# BLUENRG-345_REV1_Sheet1.net
KiCad netlist of a schematic drawn in Altium Designer
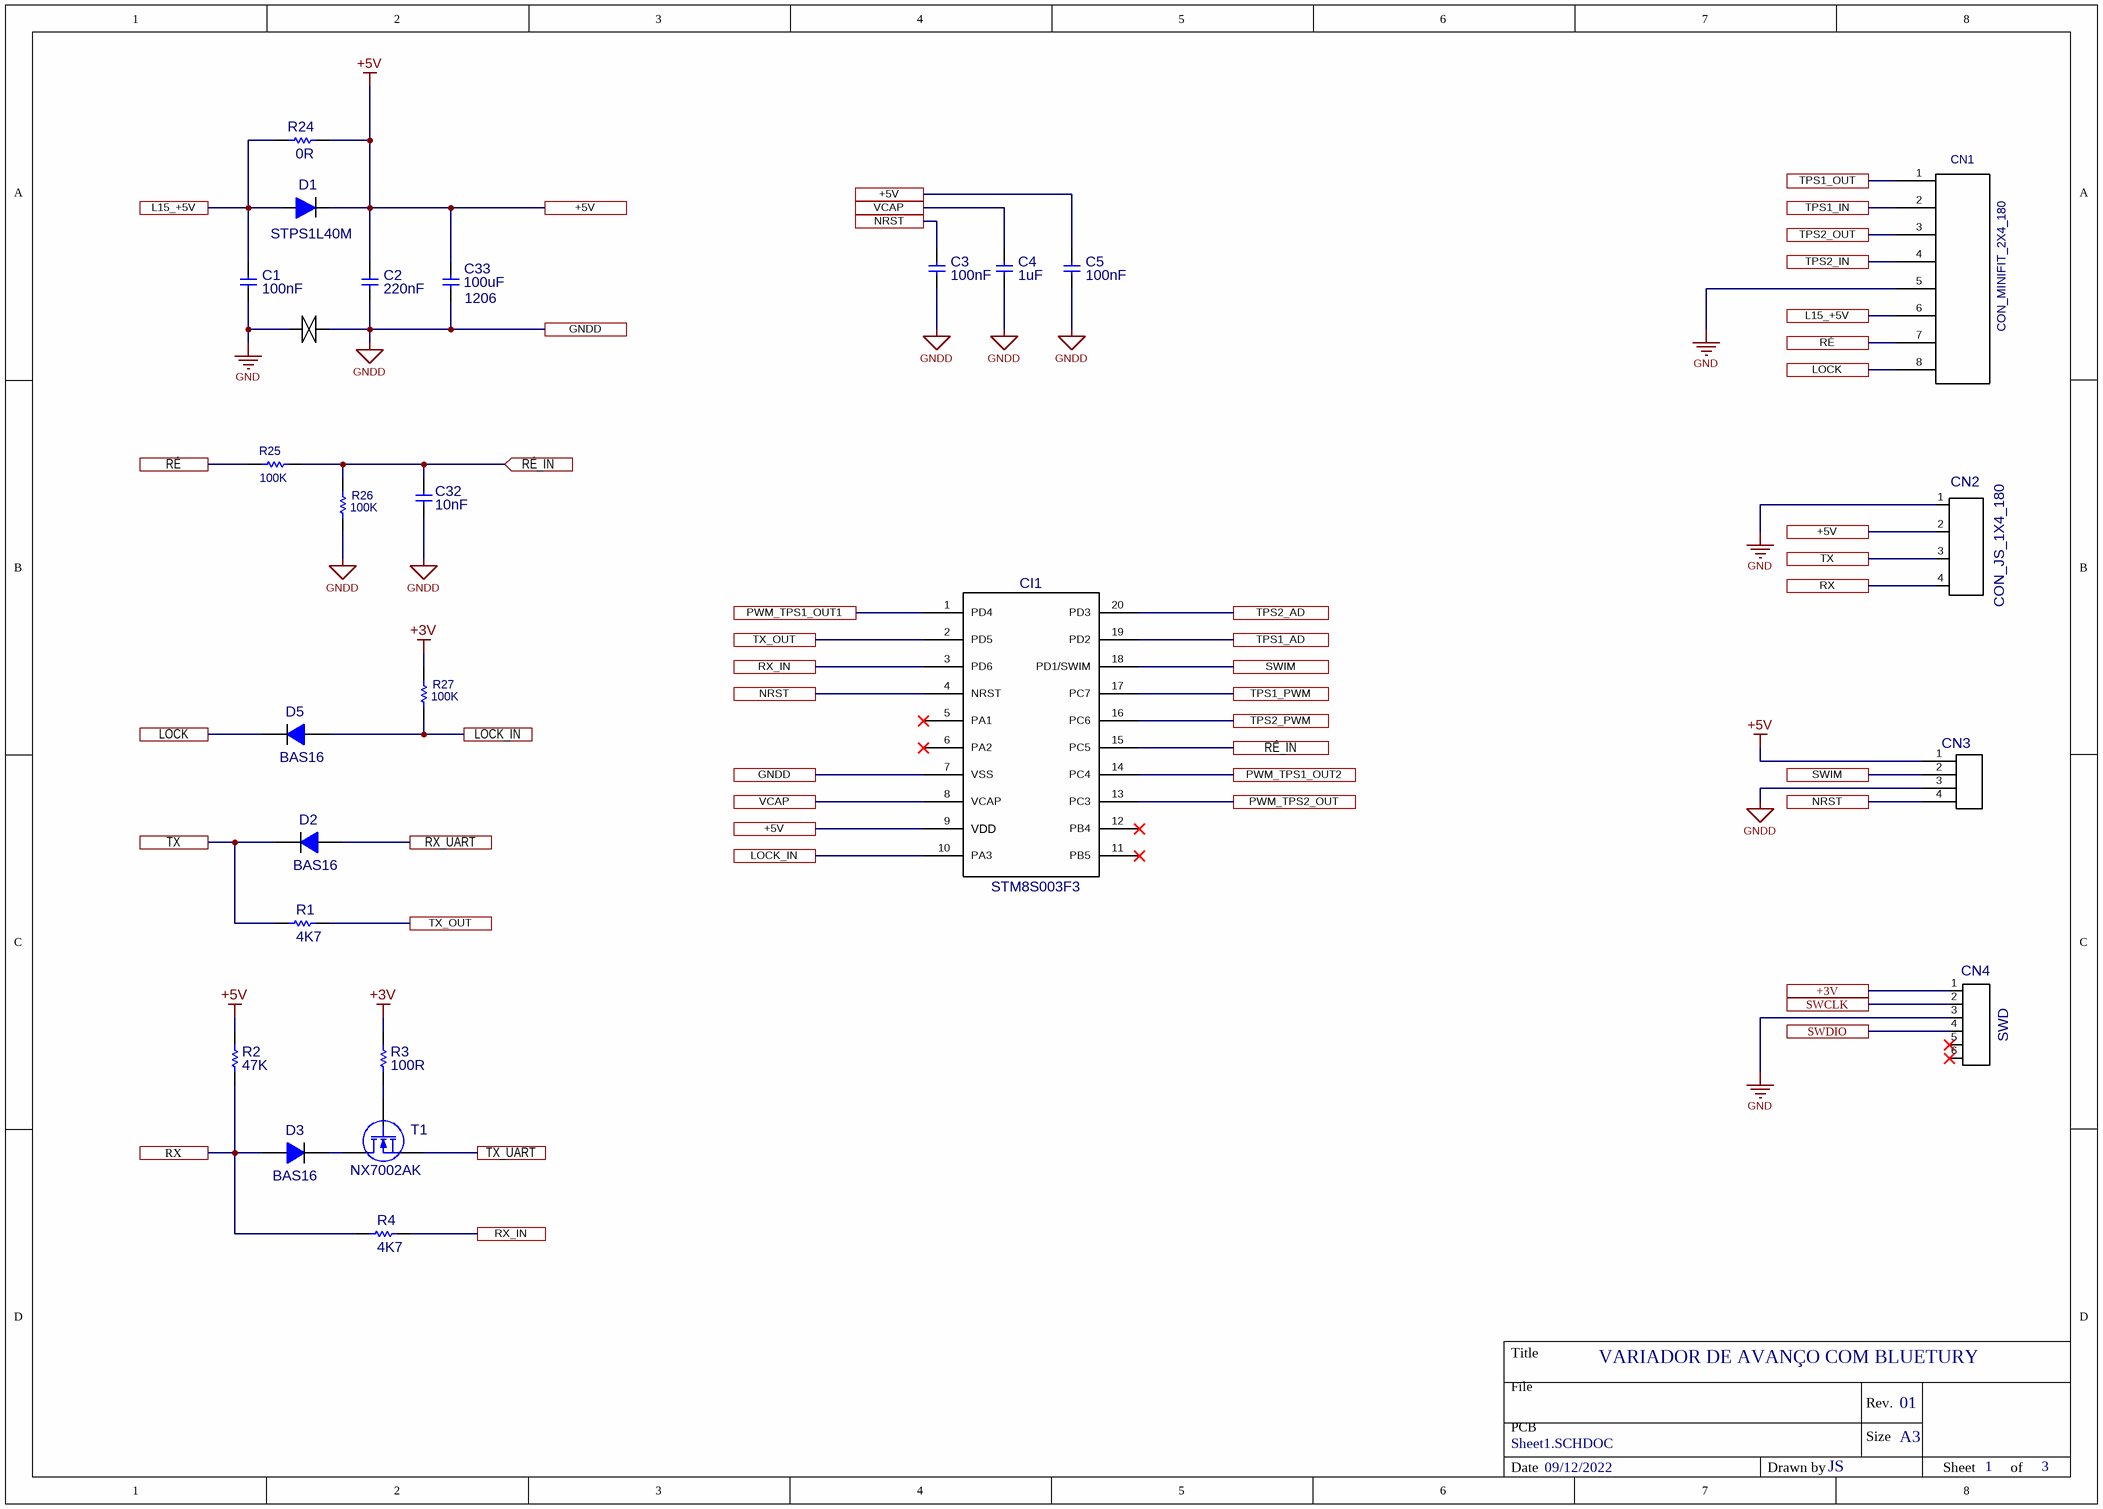
[diagram p0: BLUENRG-345_REV1_Sheet1.SchDoc]

(export (version "E")
  (design (tool "Eeschema 10.0.6"))
  (components
    (comp (ref "C1")
      (value "100nF")
      (footprint "C0402_REV1")
      (description "CAPACITOR 0402 100NF / 50V X7R 10%")
      (fields (field (name "Comment") "C0402"))
      (libsource (lib "SMD_Geral") (part "CAP_0402 100nF 10% 50V X7R"))
    )
    (comp (ref "C2")
      (value "220nF")
      (footprint "C0402_REV1")
      (description "CAPACITOR 0402 220NF / 16V X7R 10%")
      (fields (field (name "Comment") "C0402"))
      (libsource (lib "SMD_Geral") (part "CAP_0402 220nF 10% 16V X7R"))
    )
    (comp (ref "C3")
      (value "100nF")
      (footprint "C0402_REV1")
      (description "CAPACITOR 0402 100NF / 50V X7R 10%")
      (fields (field (name "Comment") "C0402"))
      (libsource (lib "SMD_Geral") (part "CAP_0402 100nF 10% 50V X7R"))
    )
    (comp (ref "C4")
      (value "1uF")
      (footprint "C0402_REV1")
      (description "CAPACITOR 0402 1UF / 16V X6S 10%")
      (fields (field (name "Comment") "C0402"))
      (libsource (lib "SMD_Geral") (part "CAP_0402 1uF 10% 16V X6S"))
    )
    (comp (ref "C5")
      (value "100nF")
      (footprint "C0402_REV1")
      (description "CAPACITOR 0402 100NF / 50V X7R 10%")
      (fields (field (name "Comment") "C0402"))
      (libsource (lib "SMD_Geral") (part "CAP_0402 100nF 10% 50V X7R"))
    )
    (comp (ref "C32")
      (value "10nF")
      (footprint "C0402_REV1")
      (description "CAPACITOR 0402 10NF / 25V X7R 5%")
      (fields (field (name "Comment") "C0402"))
      (libsource (lib "*") (part "CAP_0402 10nF 5% 25V X7R"))
    )
    (comp (ref "C33")
      (value "100uF")
      (footprint "C1206_rev1")
      (description "CAPACITOR 1206 100UF / 6V3 X5R 20%")
      (fields (field (name "ENCAPSULAMENTO") "1206") (field (name "Comment") "C1206"))
      (libsource (lib "SMD_Geral") (part "CAP_1206 100uF 6V3 X5R 20%"))
    )
    (comp (ref "CI1")
      (value "STM8S003F3")
      (footprint "TSSOP20")
      (description "CI MICROCONTROLADOR STM8S003F3P6")
      (fields (field (name "Comment") "CI_STM8S003F3_TSSOP20"))
      (libsource (lib "SMD_Geral") (part "CI_STM8S003F3_TSSOP20"))
    )
    (comp (ref "CN1")
      (value "CON_MINIFIT_2X4_180")
      (footprint "CONECTOR_MINIFIT_2X4_180")
      (description "CONECTOR PCI - POTENCIA MINIFIT PT 180° 2X4X4,2MM")
      (libsource (lib "PTH_Conectores") (part "CONECTOR_MINIFIT_2X4_180_PT"))
    )
    (comp (ref "CN2")
      (value "CON_JS_1X4_180")
      (footprint "CONECTOR_ 1x4 2.0mm - 180°")
      (description "CONECTOR PCI - SINAL 180° - 1X4X2,0MM")
      (libsource (lib "*") (part "CONECTOR_JS_1X4_180"))
    )
    (comp (ref "CN3")
      (value "CON_BP1X4_180")
      (footprint "CONECTOR_BP1X4_SWIM_180")
      (description "BARRA DE PINO - SECAO QUADRADA 180º 1X4X2,54MM")
      (fields (field (name "PART NUMBER") "013.07.00104"))
      (libsource (lib "PTH_Conectores") (part "CON_BPT_1X4_180"))
    )
    (comp (ref "CN4")
      (value "SWD")
      (footprint "CONECTOR_BP1X6_180")
      (description "Conector barra de pinos 1x6 180º")
      (fields (field (name "PART NUMBER") "013.07.00108") (field (name "Comment") "CON_BP1X6_180"))
      (libsource (lib "PTH_Conectores") (part "CONECTOR_BP1X6_180"))
    )
    (comp (ref "D1")
      (value "STPS1L40M")
      (footprint "DO216AA_REV1")
      (description "DIODO SCHOTTKY STPS1L40M DO2126-AA")
      (fields (field (name "Comment") "D_STPS1L40M_DO216AA"))
      (libsource (lib "*") (part "D_STPS1L40M_DO216AA"))
    )
    (comp (ref "D2")
      (value "BAS16")
      (footprint "SOD323_IPC")
      (description "DIODO DE SINAL BAS16 SOD323")
      (fields (field (name "Comment") "D_BAS16_SOD323"))
      (libsource (lib "SMD_Geral") (part "D_BAS16_SOD323"))
    )
    (comp (ref "D3")
      (value "BAS16")
      (footprint "SOD323_IPC")
      (description "DIODO DE SINAL BAS16 SOD323")
      (fields (field (name "Comment") "D_BAS16_SOD323"))
      (libsource (lib "SMD_Geral") (part "D_BAS16_SOD323"))
    )
    (comp (ref "D5")
      (value "BAS16")
      (footprint "SOD323_IPC")
      (description "DIODO DE SINAL BAS16 SOD323")
      (fields (field (name "Comment") "D_BAS16_SOD323"))
      (libsource (lib "SMD_Geral") (part "D_BAS16_SOD323"))
    )
    (comp (ref "NT1")
      (value "NET TIE 30mils")
      (footprint "NET TIE 30mils")
      (libsource (lib "SMD") (part "NET TIE 30mils"))
    )
    (comp (ref "R1")
      (value "4K7")
      (footprint "R0402_REV1")
      (description "RESISTOR 0402 4K7 1/16W 5%")
      (fields (field (name "Comment") "RES 0402 4K7 1/16W 5%"))
      (libsource (lib "SMD_Geral") (part "RES 0402 4K7 1/16W 5%"))
    )
    (comp (ref "R2")
      (value "47K")
      (footprint "R0402_REV1")
      (description "RESISTOR 0402 47K 1/16W 5%")
      (fields (field (name "Comment") "R0603"))
      (libsource (lib "SMD_Geral") (part "RES 0402 47K 1/16W 5%"))
    )
    (comp (ref "R3")
      (value "100R")
      (footprint "R0402_REV1")
      (description "RESISTOR 0402 100R 1/16W 5%")
      (fields (field (name "Comment") "R0603"))
      (libsource (lib "SMD_Geral") (part "RES 0402 100R 1/16W 5%"))
    )
    (comp (ref "R4")
      (value "4K7")
      (footprint "R0402_REV1")
      (description "RESISTOR 0402 4K7 1/16W 5%")
      (fields (field (name "Comment") "RES 0402 4K7 1/16W 5%"))
      (libsource (lib "SMD_Geral") (part "RES 0402 4K7 1/16W 5%"))
    )
    (comp (ref "R24")
      (value "0R")
      (footprint "R0402_REV1")
      (description "RESISTOR 0402 0R 1/16W 5%")
      (fields (field (name "Comment") "RES 0402 0R 1/16W 5%"))
      (libsource (lib "SMD_Geral") (part "RES 0402 0R 1/16W 5%"))
    )
    (comp (ref "R25")
      (value "100K")
      (footprint "R0402_REV1")
      (description "RESISTOR 0402 100K 1/16W 5%")
      (fields (field (name "Comment") "R0402"))
      (libsource (lib "SMD_Geral") (part "RES 0402 100K 1/16W 5%"))
    )
    (comp (ref "R26")
      (value "100K")
      (footprint "R0402_REV1")
      (description "RESISTOR 0402 100K 1/16W 5%")
      (fields (field (name "Comment") "R0402"))
      (libsource (lib "SMD_Geral") (part "RES 0402 100K 1/16W 5%"))
    )
    (comp (ref "R27")
      (value "100K")
      (footprint "R0402_REV1")
      (description "RESISTOR 0402 100K 1/16W 5%")
      (fields (field (name "Comment") "R0402"))
      (libsource (lib "SMD_Geral") (part "RES 0402 100K 1/16W 5%"))
    )
    (comp (ref "T1")
      (value "NX7002AK")
      (footprint "SOT23_REV1")
      (description "TRANSISTOR MOSFET CANAL N 60V ,19A NX7002AK")
      (libsource (lib "SMD_Geral") (part "T_NX7002AK"))
    )
  )
  (nets
    (net (code "1") (name "+3V") (class "Default")
      (node (ref "CN4") (pin "1") (pintype "passive"))
      (node (ref "R27") (pin "1") (pinfunction "1_1") (pintype "passive"))
      (node (ref "R3") (pin "2") (pinfunction "2_2") (pintype "passive"))
    )
    (net (code "2") (name "+5V") (class "Default")
      (node (ref "C2") (pin "1") (pinfunction "1_1") (pintype "passive"))
      (node (ref "C33") (pin "2") (pinfunction "2_2") (pintype "passive"))
      (node (ref "C5") (pin "1") (pinfunction "+_1") (pintype "passive"))
      (node (ref "CI1") (pin "9") (pinfunction "VDD_9") (pintype "passive"))
      (node (ref "CN2") (pin "2") (pintype "passive"))
      (node (ref "CN3") (pin "1") (pintype "passive"))
      (node (ref "D1") (pin "1") (pinfunction "K_1") (pintype "passive"))
      (node (ref "R2") (pin "2") (pinfunction "2_2") (pintype "passive"))
      (node (ref "R24") (pin "1") (pinfunction "1_1") (pintype "passive"))
    )
    (net (code "3") (name "/L15_+5V") (class "Default")
      (node (ref "C1") (pin "1") (pinfunction "+_1") (pintype "passive"))
      (node (ref "CN1") (pin "6") (pinfunction "6_6") (pintype "power_in"))
      (node (ref "D1") (pin "2") (pinfunction "A_2") (pintype "passive"))
      (node (ref "R24") (pin "2") (pinfunction "2_2") (pintype "passive"))
    )
    (net (code "4") (name "/LOCK") (class "Default")
      (node (ref "CN1") (pin "8") (pinfunction "8_8") (pintype "power_in"))
      (node (ref "D5") (pin "2") (pinfunction "K_2") (pintype "passive"))
    )
    (net (code "5") (name "/LOCK_IN") (class "Default")
      (node (ref "CI1") (pin "10") (pinfunction "PA3_10") (pintype "passive"))
      (node (ref "D5") (pin "1") (pinfunction "A_1") (pintype "passive"))
      (node (ref "R27") (pin "2") (pinfunction "2_2") (pintype "passive"))
    )
    (net (code "6") (name "/NRST") (class "Default")
      (node (ref "C3") (pin "1") (pinfunction "+_1") (pintype "passive"))
      (node (ref "CI1") (pin "4") (pinfunction "NRST_4") (pintype "passive"))
      (node (ref "CN3") (pin "4") (pintype "passive"))
    )
    (net (code "7") (name "/PWM_TPS1_OUT1") (class "Default")
      (node (ref "CI1") (pin "1") (pinfunction "PD4_1") (pintype "passive"))
    )
    (net (code "8") (name "/PWM_TPS1_OUT2") (class "Default")
      (node (ref "CI1") (pin "14") (pinfunction "PC4_14") (pintype "passive"))
    )
    (net (code "9") (name "/PWM_TPS2_OUT") (class "Default")
      (node (ref "CI1") (pin "13") (pinfunction "PC3_13") (pintype "passive"))
    )
    (net (code "10") (name "/RX") (class "Default")
      (node (ref "CN2") (pin "4") (pintype "passive"))
      (node (ref "D3") (pin "1") (pinfunction "A_1") (pintype "passive"))
      (node (ref "R2") (pin "1") (pinfunction "1_1") (pintype "passive"))
      (node (ref "R4") (pin "1") (pinfunction "1_1") (pintype "passive"))
    )
    (net (code "11") (name "/RX_IN") (class "Default")
      (node (ref "CI1") (pin "3") (pinfunction "PD6_3") (pintype "passive"))
      (node (ref "R4") (pin "2") (pinfunction "2_2") (pintype "passive"))
    )
    (net (code "12") (name "/RX_UART") (class "Default")
      (node (ref "D2") (pin "1") (pinfunction "A_1") (pintype "passive"))
    )
    (net (code "13") (name "/RÉ") (class "Default")
      (node (ref "CN1") (pin "7") (pinfunction "7_7") (pintype "power_in"))
      (node (ref "R25") (pin "2") (pinfunction "2_2") (pintype "passive"))
    )
    (net (code "14") (name "/RÉ_IN") (class "Default")
      (node (ref "C32") (pin "2") (pinfunction "2_2") (pintype "passive"))
      (node (ref "CI1") (pin "15") (pinfunction "PC5_15") (pintype "passive"))
      (node (ref "R25") (pin "1") (pinfunction "1_1") (pintype "passive"))
      (node (ref "R26") (pin "1") (pinfunction "1_1") (pintype "passive"))
    )
    (net (code "15") (name "/SWCLK") (class "Default") (node (ref "CN4") (pin "2") (pintype "passive")))
    (net (code "16") (name "/SWDIO") (class "Default") (node (ref "CN4") (pin "4") (pintype "passive")))
    (net (code "17") (name "/SWIM") (class "Default")
      (node (ref "CI1") (pin "18") (pinfunction "PD1/SWIM_18") (pintype "passive"))
      (node (ref "CN3") (pin "2") (pintype "passive"))
    )
    (net (code "18") (name "/TPS1_AD") (class "Default")
      (node (ref "CI1") (pin "19") (pinfunction "PD2_19") (pintype "passive"))
    )
    (net (code "19") (name "/TPS1_IN") (class "Default")
      (node (ref "CN1") (pin "2") (pinfunction "2_2") (pintype "power_in"))
    )
    (net (code "20") (name "/TPS1_OUT") (class "Default")
      (node (ref "CN1") (pin "1") (pinfunction "1_1") (pintype "power_in"))
    )
    (net (code "21") (name "/TPS1_PWM") (class "Default")
      (node (ref "CI1") (pin "17") (pinfunction "PC7_17") (pintype "passive"))
    )
    (net (code "22") (name "/TPS2_AD") (class "Default")
      (node (ref "CI1") (pin "20") (pinfunction "PD3_20") (pintype "passive"))
    )
    (net (code "23") (name "/TPS2_IN") (class "Default")
      (node (ref "CN1") (pin "4") (pinfunction "4_4") (pintype "power_in"))
    )
    (net (code "24") (name "/TPS2_OUT") (class "Default")
      (node (ref "CN1") (pin "3") (pinfunction "3_3") (pintype "power_in"))
    )
    (net (code "25") (name "/TPS2_PWM") (class "Default")
      (node (ref "CI1") (pin "16") (pinfunction "PC6_16") (pintype "passive"))
    )
    (net (code "26") (name "/TX") (class "Default")
      (node (ref "CN2") (pin "3") (pintype "passive"))
      (node (ref "D2") (pin "2") (pinfunction "K_2") (pintype "passive"))
      (node (ref "R1") (pin "1") (pinfunction "1_1") (pintype "passive"))
    )
    (net (code "27") (name "/TX_OUT") (class "Default")
      (node (ref "CI1") (pin "2") (pinfunction "PD5_2") (pintype "passive"))
      (node (ref "R1") (pin "2") (pinfunction "2_2") (pintype "passive"))
    )
    (net (code "28") (name "/TX_UART") (class "Default")
      (node (ref "T1") (pin "2") (pinfunction "S_2") (pintype "passive"))
    )
    (net (code "29") (name "/VCAP") (class "Default")
      (node (ref "C4") (pin "1") (pinfunction "1_1") (pintype "passive"))
      (node (ref "CI1") (pin "8") (pinfunction "VCAP_8") (pintype "passive"))
    )
    (net (code "30") (name "GND") (class "Default")
      (node (ref "C1") (pin "2") (pinfunction "-_2") (pintype "passive"))
      (node (ref "CN1") (pin "5") (pinfunction "5_5") (pintype "power_in"))
      (node (ref "CN2") (pin "1") (pintype "passive"))
      (node (ref "CN4") (pin "3") (pintype "passive"))
      (node (ref "NT1") (pin "2") (pintype "passive"))
    )
    (net (code "31") (name "GNDD") (class "Default")
      (node (ref "C2") (pin "2") (pinfunction "2_2") (pintype "passive"))
      (node (ref "C3") (pin "2") (pinfunction "-_2") (pintype "passive"))
      (node (ref "C32") (pin "1") (pinfunction "1_1") (pintype "passive"))
      (node (ref "C33") (pin "1") (pinfunction "1_1") (pintype "passive"))
      (node (ref "C4") (pin "2") (pinfunction "2_2") (pintype "passive"))
      (node (ref "C5") (pin "2") (pinfunction "-_2") (pintype "passive"))
      (node (ref "CI1") (pin "7") (pinfunction "VSS_7") (pintype "passive"))
      (node (ref "CN3") (pin "3") (pintype "passive"))
      (node (ref "NT1") (pin "1") (pintype "passive"))
      (node (ref "R26") (pin "2") (pinfunction "2_2") (pintype "passive"))
    )
    (net (code "32") (name "Net-(D3-K)") (class "Default")
      (node (ref "D3") (pin "2") (pinfunction "K_2") (pintype "passive"))
      (node (ref "T1") (pin "3") (pinfunction "D_3") (pintype "passive"))
    )
    (net (code "33") (name "Net-(T1-G)") (class "Default")
      (node (ref "R3") (pin "1") (pinfunction "1_1") (pintype "passive"))
      (node (ref "T1") (pin "1") (pinfunction "G_1") (pintype "passive"))
    )
    (net (code "34") (name "unconnected-(CI1-PA1-Pad5)") (class "Default")
      (node (ref "CI1") (pin "5") (pinfunction "PA1_5") (pintype "passive+no_connect"))
    )
    (net (code "35") (name "unconnected-(CI1-PA2-Pad6)") (class "Default")
      (node (ref "CI1") (pin "6") (pinfunction "PA2_6") (pintype "passive+no_connect"))
    )
    (net (code "36") (name "unconnected-(CI1-PB4-Pad12)") (class "Default")
      (node (ref "CI1") (pin "12") (pinfunction "PB4_12") (pintype "passive+no_connect"))
    )
    (net (code "37") (name "unconnected-(CI1-PB5-Pad11)") (class "Default")
      (node (ref "CI1") (pin "11") (pinfunction "PB5_11") (pintype "passive+no_connect"))
    )
    (net (code "38") (name "unconnected-(CN4-Pad5)") (class "Default")
      (node (ref "CN4") (pin "5") (pintype "passive"))
    )
    (net (code "39") (name "unconnected-(CN4-Pad6)") (class "Default")
      (node (ref "CN4") (pin "6") (pintype "passive"))
    )
  )
)
